# Power.net
KiCad netlist of a schematic drawn in Altium Designer
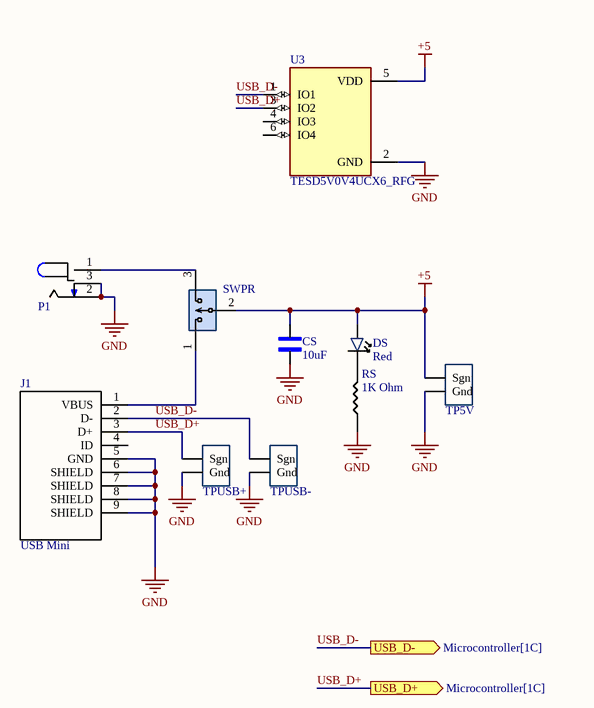
[diagram p0: Power.SchDoc]

(export (version "E")
  (design (tool "Eeschema 10.0.6"))
  (components
    (comp (ref "CS")
      (value "10uF")
      (footprint "1206_Passive_Capacitor")
      (description "10uF ±10% 50V X5R 1206 Multilayer Ceramic Capacitors MLCC - SMD/SMT RoHS")
      (fields (field (name "LCSC PART#") "C13585") (field (name "MFR PART #") "CL31A106KBHNNNE"))
      (libsource (lib "ECEN5730Lib") (part "C_10uF_1206"))
    )
    (comp (ref "DS")
      (value "Red")
      (footprint "LED_1206")
      (description "Red 621~631nm 1206 Light Emitting Diodes (LED) RoHS")
      (fields (field (name "MFR PART #") "15-21/R6C-FQ1R1B/2T") (field (name "LCSC PART#") "C93133"))
      (libsource (lib "ECEN5730Lib") (part "LED_RED_1206"))
    )
    (comp (ref "J1")
      (value "USB Mini")
      (footprint "USB_MINI_B")
      (description "Through Hole USB Connectors RoHS")
      (fields (field (name "LCSC PART#") "C46398") (field (name "MFR PART #") "920-462A2021D10102"))
      (libsource (lib "ECEN5730Lib") (part "J_USB_B_Mini"))
    )
    (comp (ref "P1")
      (value "Power Jack")
      (footprint "Power_Jack")
      (description "Power Barrel Connector Jack 2.10mm ID (0.083\"), 5.50mm OD (0.217\") Through Hole, Right Angle")
      (fields (field (name "MFR PART #") "PJ-102A") (field (name "LCSC PART#") "C136744"))
      (libsource (lib "ECEN5730Lib") (part "P_Power Jack"))
    )
    (comp (ref "RS")
      (value "1K Ohm")
      (footprint "1206_Passive_Resitor")
      (description "CHIP RESISTOR - SURFACE MOUNT 1KOHMS ±1% 1/4W 1206 ROHS")
      (fields (field (name "MFR PART #") "RNCP1206FTD1K00CT") (field (name "LCSC PART#") "C4410"))
      (libsource (lib "ECEN5730Lib") (part "R_1K_1206"))
    )
    (comp (ref "SWPR")
      (value "PREC003SAAN-RC")
      (footprint "3_PIN_100mil")
      (description "Connector Header Through Hole 3 position 0.100\" (2.54mm)")
      (fields (field (name "LCSC PART#") "C49257"))
      (libsource (lib "ECEN5730Lib") (part "SW_3Pin_100mil_Switch"))
    )
    (comp (ref "TP5V")
      (value "10x Probe TP")
      (footprint "TP10x_Probe")
      (description "Test Point 300 mil centers")
      (libsource (lib "ECEN5730Lib") (part "TP_10x_Probe"))
    )
    (comp (ref "TPUSB+")
      (value "10x Probe TP")
      (footprint "TP10x_Probe")
      (description "Test Point 300 mil centers")
      (libsource (lib "ECEN5730Lib") (part "TP_10x_Probe"))
    )
    (comp (ref "TPUSB-")
      (value "10x Probe TP")
      (footprint "TP10x_Probe")
      (description "Test Point 300 mil centers")
      (libsource (lib "ECEN5730Lib") (part "TP_10x_Probe"))
    )
    (comp (ref "U3")
      (value "TESD5V0V4UCX6_RFG")
      (footprint "SOT95P280X145-6N")
      (description "SOT-26, 5V, 75W, 0.6pF, ESD Protection")
      (fields (field (name "MF") "Taiwan Semiconductor") (field (name "MP") "TESD5V0V4UCX6 RFG"))
      (libsource (lib "TESD5V0V4UCX6_RFG") (part "TESD5V0V4UCX6_RFG"))
    )
  )
  (nets
    (net (code "1") (name "+5") (class "Default")
      (node (ref "CS") (pin "2") (pinfunction "2_2") (pintype "passive"))
      (node (ref "DS") (pin "1") (pinfunction "1_1") (pintype "passive"))
      (node (ref "SWPR") (pin "2") (pinfunction "2_2") (pintype "passive"))
      (node (ref "TP5V") (pin "1") (pinfunction "Sgn_1") (pintype "passive"))
      (node (ref "U3") (pin "5") (pinfunction "VDD_5") (pintype "power_in"))
    )
    (net (code "2") (name "/USB_D+") (class "Default")
      (node (ref "J1") (pin "3") (pinfunction "D+_3") (pintype "passive"))
      (node (ref "TPUSB+") (pin "1") (pinfunction "Sgn_1") (pintype "passive"))
      (node (ref "U3") (pin "3") (pinfunction "IO2_3") (pintype "bidirectional"))
    )
    (net (code "3") (name "/USB_D-") (class "Default")
      (node (ref "J1") (pin "2") (pinfunction "D-_2") (pintype "passive"))
      (node (ref "TPUSB-") (pin "1") (pinfunction "Sgn_1") (pintype "passive"))
      (node (ref "U3") (pin "1") (pinfunction "IO1_1") (pintype "bidirectional"))
    )
    (net (code "4") (name "GND") (class "Default")
      (node (ref "CS") (pin "1") (pinfunction "1_1") (pintype "passive"))
      (node (ref "J1") (pin "5") (pinfunction "GND_5") (pintype "passive"))
      (node (ref "J1") (pin "6") (pinfunction "SHIELD_6") (pintype "passive"))
      (node (ref "J1") (pin "7") (pinfunction "SHIELD_7") (pintype "passive"))
      (node (ref "J1") (pin "8") (pinfunction "SHIELD_8") (pintype "passive"))
      (node (ref "J1") (pin "9") (pinfunction "SHIELD_9") (pintype "passive"))
      (node (ref "P1") (pin "2") (pinfunction "2_2") (pintype "power_in"))
      (node (ref "P1") (pin "3") (pinfunction "3_3") (pintype "power_in"))
      (node (ref "RS") (pin "1") (pinfunction "1_1") (pintype "passive"))
      (node (ref "TP5V") (pin "2") (pinfunction "Gnd_2") (pintype "passive"))
      (node (ref "TPUSB+") (pin "2") (pinfunction "Gnd_2") (pintype "passive"))
      (node (ref "TPUSB-") (pin "2") (pinfunction "Gnd_2") (pintype "passive"))
      (node (ref "U3") (pin "2") (pinfunction "GND_2") (pintype "power_in"))
    )
    (net (code "5") (name "Net-(DS-Pad2)") (class "Default")
      (node (ref "DS") (pin "2") (pinfunction "2_2") (pintype "passive"))
      (node (ref "RS") (pin "2") (pinfunction "2_2") (pintype "passive"))
    )
    (net (code "6") (name "Net-(J1-VBUS)") (class "Default")
      (node (ref "J1") (pin "1") (pinfunction "VBUS_1") (pintype "passive"))
      (node (ref "SWPR") (pin "1") (pinfunction "1_1") (pintype "passive"))
    )
    (net (code "7") (name "Net-(P1-Pad1)") (class "Default")
      (node (ref "P1") (pin "1") (pinfunction "1_1") (pintype "power_in"))
      (node (ref "SWPR") (pin "3") (pinfunction "3_3") (pintype "passive"))
    )
    (net (code "8") (name "unconnected-(J1-ID-Pad4)") (class "Default")
      (node (ref "J1") (pin "4") (pinfunction "ID_4") (pintype "passive"))
    )
    (net (code "9") (name "unconnected-(U3-IO3-Pad4)") (class "Default")
      (node (ref "U3") (pin "4") (pinfunction "IO3_4") (pintype "bidirectional"))
    )
    (net (code "10") (name "unconnected-(U3-IO4-Pad6)") (class "Default")
      (node (ref "U3") (pin "6") (pinfunction "IO4_6") (pintype "bidirectional"))
    )
  )
)
